# IDC_connectors.net
KiCad netlist of a schematic drawn in Altium Designer
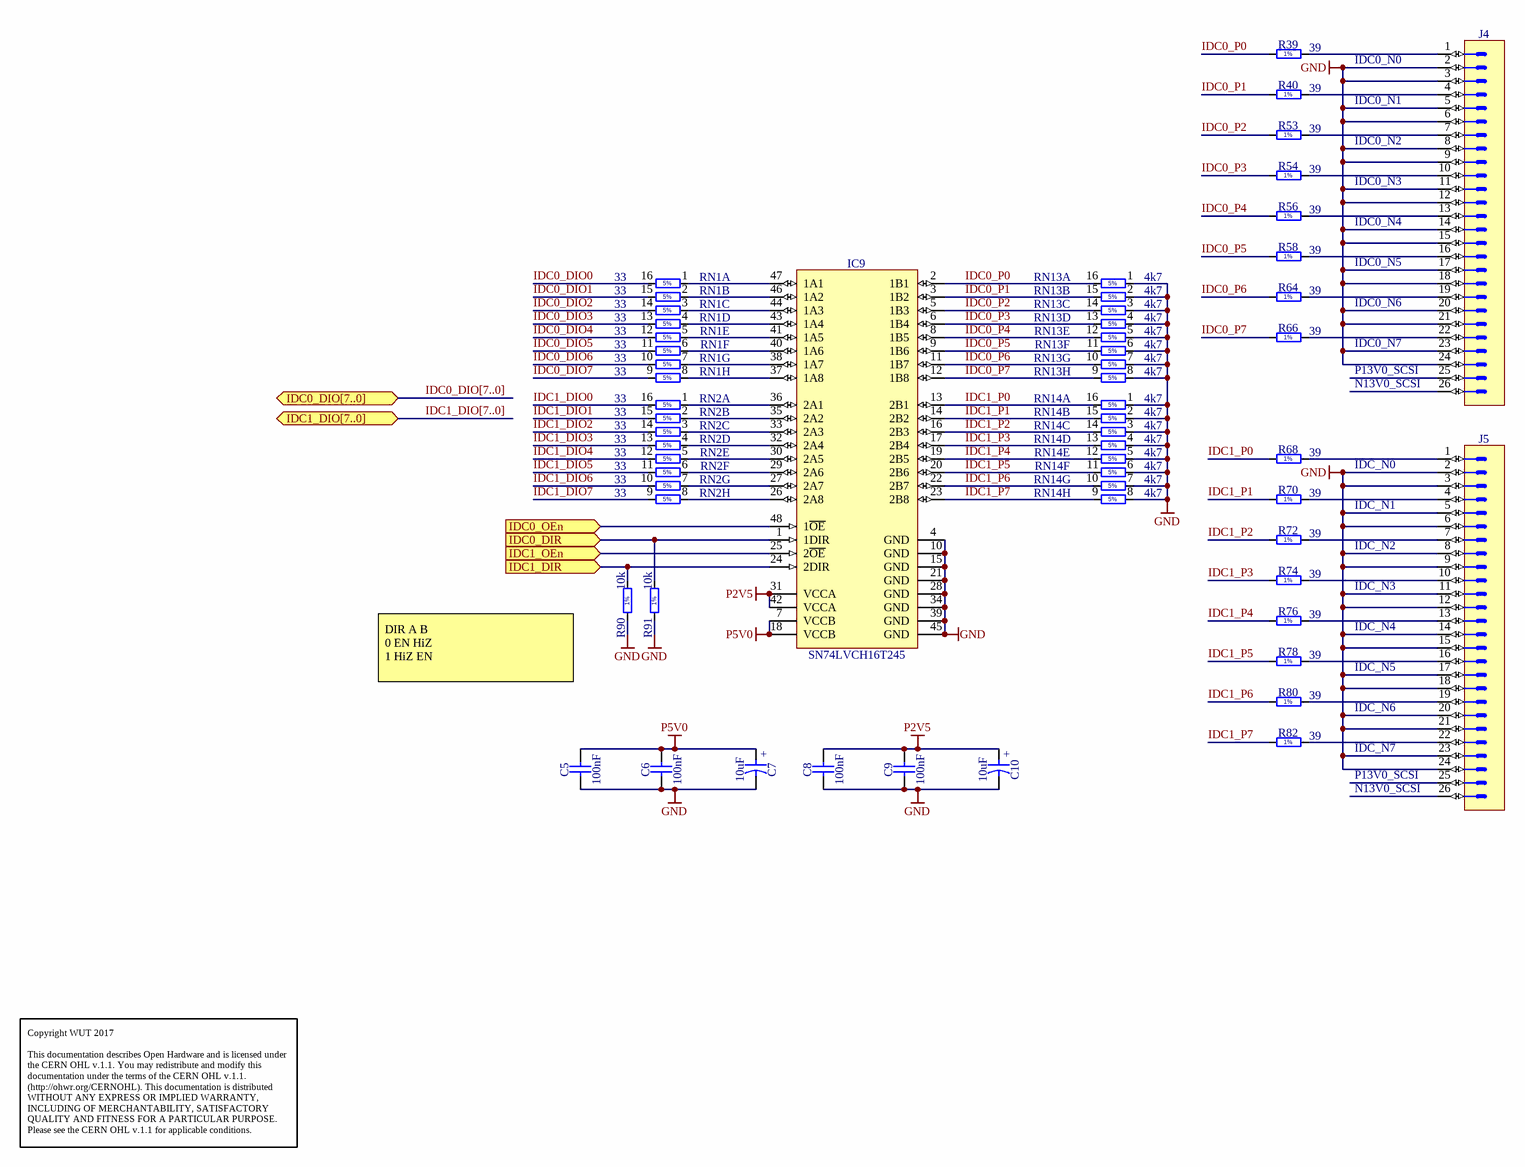
[diagram p0: IDC_connectors.SchDoc]

(export (version "E")
  (design (tool "Eeschema 10.0.6"))
  (components
    (comp (ref "C5")
      (value "100nF")
      (footprint "CAPC1005X55N")
      (description "Non-polarised capacitor")
      (fields
        (field (name "PART NUMBER") "CC0402_100NF_16V_10%_X5R")
        (field (name "VOLTAGE") "16V")
        (field (name "AUTHOR") "CERN DEM JLC")
      )
      (libsource (lib "Capacitors") (part "Capacitor - non polarized"))
    )
    (comp (ref "C6")
      (value "100nF")
      (footprint "CAPC1005X55N")
      (description "Non-polarised capacitor")
      (fields
        (field (name "PART NUMBER") "CC0402_100NF_16V_10%_X5R")
        (field (name "VOLTAGE") "16V")
        (field (name "AUTHOR") "CERN DEM JLC")
      )
      (libsource (lib "Capacitors") (part "Capacitor - non polarized"))
    )
    (comp (ref "C7")
      (value "10uF")
      (footprint "CAPAE430X540N")
      (description "Polarised capacitor")
      (fields
        (field (name "PART NUMBER") "CAE430-540_10UF_16V_20%")
        (field (name "VOLTAGE") "16V")
        (field (name "AUTHOR") "CERN DEM JLC")
      )
      (libsource (lib "Capacitors") (part "Capacitor - polarized"))
    )
    (comp (ref "C8")
      (value "100nF")
      (footprint "CAPC1005X55N")
      (description "Non-polarised capacitor")
      (fields
        (field (name "PART NUMBER") "CC0402_100NF_16V_10%_X5R")
        (field (name "VOLTAGE") "16V")
        (field (name "AUTHOR") "CERN DEM JLC")
      )
      (libsource (lib "Capacitors") (part "Capacitor - non polarized"))
    )
    (comp (ref "C9")
      (value "100nF")
      (footprint "CAPC1005X55N")
      (description "Non-polarised capacitor")
      (fields
        (field (name "PART NUMBER") "CC0402_100NF_16V_10%_X5R")
        (field (name "VOLTAGE") "16V")
        (field (name "AUTHOR") "CERN DEM JLC")
      )
      (libsource (lib "Capacitors") (part "Capacitor - non polarized"))
    )
    (comp (ref "C10")
      (value "10uF")
      (footprint "CAPAE430X540N")
      (description "Polarised capacitor")
      (fields
        (field (name "PART NUMBER") "CAE430-540_10UF_16V_20%")
        (field (name "VOLTAGE") "16V")
        (field (name "AUTHOR") "CERN DEM JLC")
      )
      (libsource (lib "Capacitors") (part "Capacitor - polarized"))
    )
    (comp (ref "IC9")
      (value "SN74LVCH16T245")
      (footprint "SOP50P810X120-48N")
      (description "16-Bit Dual-Supply Bus Transceiver With Configurable Voltage Translation And 3-State Outputs")
      (fields
        (field (name "PART NUMBER") "SN74LVCH16T245DGGR")
        (field (name "MANUFACTURER") "TEXAS INSTRUMENTS")
        (field (name "AUTHOR") "GK")
      )
      (libsource (lib "LIBRARY_SCH") (part "74LVCH16T245"))
    )
    (comp (ref "J4")
      (value "Header 26")
      (footprint "3M_N2526-6003RB")
      (description "Connector 26 Male")
      (fields
        (field (name "PART NUMBER") "3M_N2526-6003RB")
        (field (name "MANUFACTURER") "3M")
        (field (name "AUTHOR") "CERN DEM JLC")
      )
      (libsource (lib "Connectors") (part "Connector 26 Male"))
    )
    (comp (ref "J5")
      (value "Header 26")
      (footprint "3M_N2526-6003RB")
      (description "Connector 26 Male")
      (fields
        (field (name "PART NUMBER") "3M_N2526-6003RB")
        (field (name "MANUFACTURER") "3M")
        (field (name "AUTHOR") "CERN DEM JLC")
      )
      (libsource (lib "Connectors") (part "Connector 26 Male"))
    )
    (comp (ref "R39")
      (value "39")
      (footprint "RESC2012X60N")
      (description "Resistor - 1%")
      (fields
        (field (name "PART NUMBER") "R0805_39R_1%_0.125W_100PPM")
        (field (name "POWER") "0.125W")
        (field (name "AUTHOR") "CERN DEM JLC")
      )
      (libsource (lib "Resistors") (part "Resistor - 1%"))
    )
    (comp (ref "R40")
      (value "39")
      (footprint "RESC2012X60N")
      (description "Resistor - 1%")
      (fields
        (field (name "PART NUMBER") "R0805_39R_1%_0.125W_100PPM")
        (field (name "POWER") "0.125W")
        (field (name "AUTHOR") "CERN DEM JLC")
      )
      (libsource (lib "Resistors") (part "Resistor - 1%"))
    )
    (comp (ref "R53")
      (value "39")
      (footprint "RESC2012X60N")
      (description "Resistor - 1%")
      (fields
        (field (name "PART NUMBER") "R0805_39R_1%_0.125W_100PPM")
        (field (name "POWER") "0.125W")
        (field (name "AUTHOR") "CERN DEM JLC")
      )
      (libsource (lib "Resistors") (part "Resistor - 1%"))
    )
    (comp (ref "R54")
      (value "39")
      (footprint "RESC2012X60N")
      (description "Resistor - 1%")
      (fields
        (field (name "PART NUMBER") "R0805_39R_1%_0.125W_100PPM")
        (field (name "POWER") "0.125W")
        (field (name "AUTHOR") "CERN DEM JLC")
      )
      (libsource (lib "Resistors") (part "Resistor - 1%"))
    )
    (comp (ref "R56")
      (value "39")
      (footprint "RESC2012X60N")
      (description "Resistor - 1%")
      (fields
        (field (name "PART NUMBER") "R0805_39R_1%_0.125W_100PPM")
        (field (name "POWER") "0.125W")
        (field (name "AUTHOR") "CERN DEM JLC")
      )
      (libsource (lib "Resistors") (part "Resistor - 1%"))
    )
    (comp (ref "R58")
      (value "39")
      (footprint "RESC2012X60N")
      (description "Resistor - 1%")
      (fields
        (field (name "PART NUMBER") "R0805_39R_1%_0.125W_100PPM")
        (field (name "POWER") "0.125W")
        (field (name "AUTHOR") "CERN DEM JLC")
      )
      (libsource (lib "Resistors") (part "Resistor - 1%"))
    )
    (comp (ref "R64")
      (value "39")
      (footprint "RESC2012X60N")
      (description "Resistor - 1%")
      (fields
        (field (name "PART NUMBER") "R0805_39R_1%_0.125W_100PPM")
        (field (name "POWER") "0.125W")
        (field (name "AUTHOR") "CERN DEM JLC")
      )
      (libsource (lib "Resistors") (part "Resistor - 1%"))
    )
    (comp (ref "R66")
      (value "39")
      (footprint "RESC2012X60N")
      (description "Resistor - 1%")
      (fields
        (field (name "PART NUMBER") "R0805_39R_1%_0.125W_100PPM")
        (field (name "POWER") "0.125W")
        (field (name "AUTHOR") "CERN DEM JLC")
      )
      (libsource (lib "Resistors") (part "Resistor - 1%"))
    )
    (comp (ref "R68")
      (value "39")
      (footprint "RESC2012X60N")
      (description "Resistor - 1%")
      (fields
        (field (name "PART NUMBER") "R0805_39R_1%_0.125W_100PPM")
        (field (name "POWER") "0.125W")
        (field (name "AUTHOR") "CERN DEM JLC")
      )
      (libsource (lib "Resistors") (part "Resistor - 1%"))
    )
    (comp (ref "R70")
      (value "39")
      (footprint "RESC2012X60N")
      (description "Resistor - 1%")
      (fields
        (field (name "PART NUMBER") "R0805_39R_1%_0.125W_100PPM")
        (field (name "POWER") "0.125W")
        (field (name "AUTHOR") "CERN DEM JLC")
      )
      (libsource (lib "Resistors") (part "Resistor - 1%"))
    )
    (comp (ref "R72")
      (value "39")
      (footprint "RESC2012X60N")
      (description "Resistor - 1%")
      (fields
        (field (name "PART NUMBER") "R0805_39R_1%_0.125W_100PPM")
        (field (name "POWER") "0.125W")
        (field (name "AUTHOR") "CERN DEM JLC")
      )
      (libsource (lib "Resistors") (part "Resistor - 1%"))
    )
    (comp (ref "R74")
      (value "39")
      (footprint "RESC2012X60N")
      (description "Resistor - 1%")
      (fields
        (field (name "PART NUMBER") "R0805_39R_1%_0.125W_100PPM")
        (field (name "POWER") "0.125W")
        (field (name "AUTHOR") "CERN DEM JLC")
      )
      (libsource (lib "Resistors") (part "Resistor - 1%"))
    )
    (comp (ref "R76")
      (value "39")
      (footprint "RESC2012X60N")
      (description "Resistor - 1%")
      (fields
        (field (name "PART NUMBER") "R0805_39R_1%_0.125W_100PPM")
        (field (name "POWER") "0.125W")
        (field (name "AUTHOR") "CERN DEM JLC")
      )
      (libsource (lib "Resistors") (part "Resistor - 1%"))
    )
    (comp (ref "R78")
      (value "39")
      (footprint "RESC2012X60N")
      (description "Resistor - 1%")
      (fields
        (field (name "PART NUMBER") "R0805_39R_1%_0.125W_100PPM")
        (field (name "POWER") "0.125W")
        (field (name "AUTHOR") "CERN DEM JLC")
      )
      (libsource (lib "Resistors") (part "Resistor - 1%"))
    )
    (comp (ref "R80")
      (value "39")
      (footprint "RESC2012X60N")
      (description "Resistor - 1%")
      (fields
        (field (name "PART NUMBER") "R0805_39R_1%_0.125W_100PPM")
        (field (name "POWER") "0.125W")
        (field (name "AUTHOR") "CERN DEM JLC")
      )
      (libsource (lib "Resistors") (part "Resistor - 1%"))
    )
    (comp (ref "R82")
      (value "39")
      (footprint "RESC2012X60N")
      (description "Resistor - 1%")
      (fields
        (field (name "PART NUMBER") "R0805_39R_1%_0.125W_100PPM")
        (field (name "POWER") "0.125W")
        (field (name "AUTHOR") "CERN DEM JLC")
      )
      (libsource (lib "Resistors") (part "Resistor - 1%"))
    )
    (comp (ref "R90")
      (value "10k")
      (footprint "RESC1005X40N")
      (description "Resistor - 1%")
      (fields
        (field (name "PART NUMBER") "R0402_10K_1%_0.0625W_100PPM")
        (field (name "POWER") "0.0625W")
        (field (name "AUTHOR") "CERN DEM JLC")
      )
      (libsource (lib "Resistors") (part "Resistor - 1%"))
    )
    (comp (ref "R91")
      (value "10k")
      (footprint "RESC1005X40N")
      (description "Resistor - 1%")
      (fields
        (field (name "PART NUMBER") "R0402_10K_1%_0.0625W_100PPM")
        (field (name "POWER") "0.0625W")
        (field (name "AUTHOR") "CERN DEM JLC")
      )
      (libsource (lib "Resistors") (part "Resistor - 1%"))
    )
    (comp (ref "RN1")
      (value "33")
      (footprint "RN_YAGEO_YC248")
      (description "DIL16 Resistor Network 8 Isolated Resistor 5%")
      (fields
        (field (name "PART NUMBER") "RN_33R_YAGEO_YC248-JR-0733RL")
        (field (name "POWER") "0.062W")
        (field (name "AUTHOR") "CERN DEM JLC")
      )
      (libsource (lib "Resistors") (part "RN DIL16_8xR_Isolated_5%"))
    )
    (comp (ref "RN2")
      (value "33")
      (footprint "RN_YAGEO_YC248")
      (description "DIL16 Resistor Network 8 Isolated Resistor 5%")
      (fields
        (field (name "PART NUMBER") "RN_33R_YAGEO_YC248-JR-0733RL")
        (field (name "POWER") "0.062W")
        (field (name "AUTHOR") "CERN DEM JLC")
      )
      (libsource (lib "Resistors") (part "RN DIL16_8xR_Isolated_5%"))
    )
    (comp (ref "RN13")
      (value "4k7")
      (footprint "RN_YAGEO_YC248")
      (description "8x Resistor Network  Isolated Resistor 5%")
      (fields
        (field (name "PART NUMBER") "RN_33R_YAGEO_YC248-JR-074K7L")
        (field (name "POWER") "0.062W")
        (field (name "AUTHOR") "GK")
      )
      (libsource (lib "LIBRARY_SCH") (part "RES_RN_4K7_YAGEO_YC248-JR-074K7L"))
    )
    (comp (ref "RN14")
      (value "4k7")
      (footprint "RN_YAGEO_YC248")
      (description "8x Resistor Network  Isolated Resistor 5%")
      (fields
        (field (name "PART NUMBER") "RN_33R_YAGEO_YC248-JR-074K7L")
        (field (name "POWER") "0.062W")
        (field (name "AUTHOR") "GK")
      )
      (libsource (lib "LIBRARY_SCH") (part "RES_RN_4K7_YAGEO_YC248-JR-074K7L"))
    )
  )
  (nets
    (net (code "1") (name "/IDC0_DIO0") (class "Default")
      (node (ref "RN1") (pin "16") (pinfunction "16_16") (pintype "passive"))
    )
    (net (code "2") (name "/IDC0_DIO1") (class "Default")
      (node (ref "RN1") (pin "15") (pinfunction "15_15") (pintype "passive"))
    )
    (net (code "3") (name "/IDC0_DIO2") (class "Default")
      (node (ref "RN1") (pin "14") (pinfunction "14_14") (pintype "passive"))
    )
    (net (code "4") (name "/IDC0_DIO3") (class "Default")
      (node (ref "RN1") (pin "13") (pinfunction "13_13") (pintype "passive"))
    )
    (net (code "5") (name "/IDC0_DIO4") (class "Default")
      (node (ref "RN1") (pin "12") (pinfunction "12_12") (pintype "passive"))
    )
    (net (code "6") (name "/IDC0_DIO5") (class "Default")
      (node (ref "RN1") (pin "11") (pinfunction "11_11") (pintype "passive"))
    )
    (net (code "7") (name "/IDC0_DIO6") (class "Default")
      (node (ref "RN1") (pin "10") (pinfunction "10_10") (pintype "passive"))
    )
    (net (code "8") (name "/IDC0_DIO7") (class "Default")
      (node (ref "RN1") (pin "9") (pinfunction "9_9") (pintype "passive"))
    )
    (net (code "10") (name "/IDC0_DIR") (class "Default")
      (node (ref "IC9") (pin "1") (pinfunction "1DIR_1") (pintype "input"))
      (node (ref "R91") (pin "2") (pinfunction "2_2") (pintype "passive"))
    )
    (net (code "11") (name "/IDC0_OEn") (class "Default")
      (node (ref "IC9") (pin "48") (pinfunction "1~{OE}_48") (pintype "input"))
    )
    (net (code "12") (name "/IDC0_P0") (class "Default")
      (node (ref "IC9") (pin "2") (pinfunction "1B1_2") (pintype "bidirectional"))
      (node (ref "R39") (pin "1") (pinfunction "1_1") (pintype "passive"))
      (node (ref "RN13") (pin "16") (pinfunction "16_16") (pintype "passive"))
    )
    (net (code "13") (name "/IDC0_P1") (class "Default")
      (node (ref "IC9") (pin "3") (pinfunction "1B2_3") (pintype "bidirectional"))
      (node (ref "R40") (pin "1") (pinfunction "1_1") (pintype "passive"))
      (node (ref "RN13") (pin "15") (pinfunction "15_15") (pintype "passive"))
    )
    (net (code "14") (name "/IDC0_P2") (class "Default")
      (node (ref "IC9") (pin "5") (pinfunction "1B3_5") (pintype "bidirectional"))
      (node (ref "R53") (pin "1") (pinfunction "1_1") (pintype "passive"))
      (node (ref "RN13") (pin "14") (pinfunction "14_14") (pintype "passive"))
    )
    (net (code "15") (name "/IDC0_P3") (class "Default")
      (node (ref "IC9") (pin "6") (pinfunction "1B4_6") (pintype "bidirectional"))
      (node (ref "R54") (pin "1") (pinfunction "1_1") (pintype "passive"))
      (node (ref "RN13") (pin "13") (pinfunction "13_13") (pintype "passive"))
    )
    (net (code "16") (name "/IDC0_P4") (class "Default")
      (node (ref "IC9") (pin "8") (pinfunction "1B5_8") (pintype "bidirectional"))
      (node (ref "R56") (pin "1") (pinfunction "1_1") (pintype "passive"))
      (node (ref "RN13") (pin "12") (pinfunction "12_12") (pintype "passive"))
    )
    (net (code "17") (name "/IDC0_P5") (class "Default")
      (node (ref "IC9") (pin "9") (pinfunction "1B6_9") (pintype "bidirectional"))
      (node (ref "R58") (pin "1") (pinfunction "1_1") (pintype "passive"))
      (node (ref "RN13") (pin "11") (pinfunction "11_11") (pintype "passive"))
    )
    (net (code "18") (name "/IDC0_P6") (class "Default")
      (node (ref "IC9") (pin "11") (pinfunction "1B7_11") (pintype "bidirectional"))
      (node (ref "R64") (pin "1") (pinfunction "1_1") (pintype "passive"))
      (node (ref "RN13") (pin "10") (pinfunction "10_10") (pintype "passive"))
    )
    (net (code "19") (name "/IDC0_P7") (class "Default")
      (node (ref "IC9") (pin "12") (pinfunction "1B8_12") (pintype "bidirectional"))
      (node (ref "R66") (pin "1") (pinfunction "1_1") (pintype "passive"))
      (node (ref "RN13") (pin "9") (pinfunction "9_9") (pintype "passive"))
    )
    (net (code "20") (name "/IDC1_DIO0") (class "Default")
      (node (ref "RN2") (pin "16") (pinfunction "16_16") (pintype "passive"))
    )
    (net (code "21") (name "/IDC1_DIO1") (class "Default")
      (node (ref "RN2") (pin "15") (pinfunction "15_15") (pintype "passive"))
    )
    (net (code "22") (name "/IDC1_DIO2") (class "Default")
      (node (ref "RN2") (pin "14") (pinfunction "14_14") (pintype "passive"))
    )
    (net (code "23") (name "/IDC1_DIO3") (class "Default")
      (node (ref "RN2") (pin "13") (pinfunction "13_13") (pintype "passive"))
    )
    (net (code "24") (name "/IDC1_DIO4") (class "Default")
      (node (ref "RN2") (pin "12") (pinfunction "12_12") (pintype "passive"))
    )
    (net (code "25") (name "/IDC1_DIO5") (class "Default")
      (node (ref "RN2") (pin "11") (pinfunction "11_11") (pintype "passive"))
    )
    (net (code "26") (name "/IDC1_DIO6") (class "Default")
      (node (ref "RN2") (pin "10") (pinfunction "10_10") (pintype "passive"))
    )
    (net (code "27") (name "/IDC1_DIO7") (class "Default")
      (node (ref "RN2") (pin "9") (pinfunction "9_9") (pintype "passive"))
    )
    (net (code "29") (name "/IDC1_DIR") (class "Default")
      (node (ref "IC9") (pin "24") (pinfunction "2DIR_24") (pintype "input"))
      (node (ref "R90") (pin "2") (pinfunction "2_2") (pintype "passive"))
    )
    (net (code "30") (name "/IDC1_OEn") (class "Default")
      (node (ref "IC9") (pin "25") (pinfunction "2~{OE}_25") (pintype "input"))
    )
    (net (code "31") (name "/IDC1_P0") (class "Default")
      (node (ref "IC9") (pin "13") (pinfunction "2B1_13") (pintype "bidirectional"))
      (node (ref "R68") (pin "1") (pinfunction "1_1") (pintype "passive"))
      (node (ref "RN14") (pin "16") (pinfunction "16_16") (pintype "passive"))
    )
    (net (code "32") (name "/IDC1_P1") (class "Default")
      (node (ref "IC9") (pin "14") (pinfunction "2B2_14") (pintype "bidirectional"))
      (node (ref "R70") (pin "1") (pinfunction "1_1") (pintype "passive"))
      (node (ref "RN14") (pin "15") (pinfunction "15_15") (pintype "passive"))
    )
    (net (code "33") (name "/IDC1_P2") (class "Default")
      (node (ref "IC9") (pin "16") (pinfunction "2B3_16") (pintype "bidirectional"))
      (node (ref "R72") (pin "1") (pinfunction "1_1") (pintype "passive"))
      (node (ref "RN14") (pin "14") (pinfunction "14_14") (pintype "passive"))
    )
    (net (code "34") (name "/IDC1_P3") (class "Default")
      (node (ref "IC9") (pin "17") (pinfunction "2B4_17") (pintype "bidirectional"))
      (node (ref "R74") (pin "1") (pinfunction "1_1") (pintype "passive"))
      (node (ref "RN14") (pin "13") (pinfunction "13_13") (pintype "passive"))
    )
    (net (code "35") (name "/IDC1_P4") (class "Default")
      (node (ref "IC9") (pin "19") (pinfunction "2B5_19") (pintype "bidirectional"))
      (node (ref "R76") (pin "1") (pinfunction "1_1") (pintype "passive"))
      (node (ref "RN14") (pin "12") (pinfunction "12_12") (pintype "passive"))
    )
    (net (code "36") (name "/IDC1_P5") (class "Default")
      (node (ref "IC9") (pin "20") (pinfunction "2B6_20") (pintype "bidirectional"))
      (node (ref "R78") (pin "1") (pinfunction "1_1") (pintype "passive"))
      (node (ref "RN14") (pin "11") (pinfunction "11_11") (pintype "passive"))
    )
    (net (code "37") (name "/IDC1_P6") (class "Default")
      (node (ref "IC9") (pin "22") (pinfunction "2B7_22") (pintype "bidirectional"))
      (node (ref "R80") (pin "1") (pinfunction "1_1") (pintype "passive"))
      (node (ref "RN14") (pin "10") (pinfunction "10_10") (pintype "passive"))
    )
    (net (code "38") (name "/IDC1_P7") (class "Default")
      (node (ref "IC9") (pin "23") (pinfunction "2B8_23") (pintype "bidirectional"))
      (node (ref "R82") (pin "1") (pinfunction "1_1") (pintype "passive"))
      (node (ref "RN14") (pin "9") (pinfunction "9_9") (pintype "passive"))
    )
    (net (code "39") (name "GND") (class "Default")
      (node (ref "C10") (pin "2") (pinfunction "2_2") (pintype "passive"))
      (node (ref "C5") (pin "1") (pinfunction "1_1") (pintype "passive"))
      (node (ref "C6") (pin "1") (pinfunction "1_1") (pintype "passive"))
      (node (ref "C7") (pin "2") (pinfunction "2_2") (pintype "passive"))
      (node (ref "C8") (pin "1") (pinfunction "1_1") (pintype "passive"))
      (node (ref "C9") (pin "1") (pinfunction "1_1") (pintype "passive"))
      (node (ref "IC9") (pin "10") (pinfunction "GND_10") (pintype "power_in"))
      (node (ref "IC9") (pin "15") (pinfunction "GND_15") (pintype "power_in"))
      (node (ref "IC9") (pin "21") (pinfunction "GND_21") (pintype "power_in"))
      (node (ref "IC9") (pin "28") (pinfunction "GND_28") (pintype "power_in"))
      (node (ref "IC9") (pin "34") (pinfunction "GND_34") (pintype "power_in"))
      (node (ref "IC9") (pin "39") (pinfunction "GND_39") (pintype "power_in"))
      (node (ref "IC9") (pin "4") (pinfunction "GND_4") (pintype "power_in"))
      (node (ref "IC9") (pin "45") (pinfunction "GND_45") (pintype "power_in"))
      (node (ref "J4") (pin "11") (pinfunction "11_11") (pintype "bidirectional"))
      (node (ref "J4") (pin "12") (pinfunction "12_12") (pintype "bidirectional"))
      (node (ref "J4") (pin "14") (pinfunction "14_14") (pintype "bidirectional"))
      (node (ref "J4") (pin "15") (pinfunction "15_15") (pintype "bidirectional"))
      (node (ref "J4") (pin "17") (pinfunction "17_17") (pintype "bidirectional"))
      (node (ref "J4") (pin "18") (pinfunction "18_18") (pintype "bidirectional"))
      (node (ref "J4") (pin "2") (pinfunction "2_2") (pintype "bidirectional"))
      (node (ref "J4") (pin "20") (pinfunction "20_20") (pintype "bidirectional"))
      (node (ref "J4") (pin "21") (pinfunction "21_21") (pintype "bidirectional"))
      (node (ref "J4") (pin "23") (pinfunction "23_23") (pintype "bidirectional"))
      (node (ref "J4") (pin "24") (pinfunction "24_24") (pintype "bidirectional"))
      (node (ref "J4") (pin "3") (pinfunction "3_3") (pintype "bidirectional"))
      (node (ref "J4") (pin "5") (pinfunction "5_5") (pintype "bidirectional"))
      (node (ref "J4") (pin "6") (pinfunction "6_6") (pintype "bidirectional"))
      (node (ref "J4") (pin "8") (pinfunction "8_8") (pintype "bidirectional"))
      (node (ref "J4") (pin "9") (pinfunction "9_9") (pintype "bidirectional"))
      (node (ref "J5") (pin "11") (pinfunction "11_11") (pintype "bidirectional"))
      (node (ref "J5") (pin "12") (pinfunction "12_12") (pintype "bidirectional"))
      (node (ref "J5") (pin "14") (pinfunction "14_14") (pintype "bidirectional"))
      (node (ref "J5") (pin "15") (pinfunction "15_15") (pintype "bidirectional"))
      (node (ref "J5") (pin "17") (pinfunction "17_17") (pintype "bidirectional"))
      (node (ref "J5") (pin "18") (pinfunction "18_18") (pintype "bidirectional"))
      (node (ref "J5") (pin "2") (pinfunction "2_2") (pintype "bidirectional"))
      (node (ref "J5") (pin "20") (pinfunction "20_20") (pintype "bidirectional"))
      (node (ref "J5") (pin "21") (pinfunction "21_21") (pintype "bidirectional"))
      (node (ref "J5") (pin "23") (pinfunction "23_23") (pintype "bidirectional"))
      (node (ref "J5") (pin "24") (pinfunction "24_24") (pintype "bidirectional"))
      (node (ref "J5") (pin "3") (pinfunction "3_3") (pintype "bidirectional"))
      (node (ref "J5") (pin "5") (pinfunction "5_5") (pintype "bidirectional"))
      (node (ref "J5") (pin "6") (pinfunction "6_6") (pintype "bidirectional"))
      (node (ref "J5") (pin "8") (pinfunction "8_8") (pintype "bidirectional"))
      (node (ref "J5") (pin "9") (pinfunction "9_9") (pintype "bidirectional"))
      (node (ref "R90") (pin "1") (pinfunction "1_1") (pintype "passive"))
      (node (ref "R91") (pin "1") (pinfunction "1_1") (pintype "passive"))
      (node (ref "RN13") (pin "1") (pinfunction "1_1") (pintype "passive"))
      (node (ref "RN13") (pin "2") (pinfunction "2_2") (pintype "passive"))
      (node (ref "RN13") (pin "3") (pinfunction "3_3") (pintype "passive"))
      (node (ref "RN13") (pin "4") (pinfunction "4_4") (pintype "passive"))
      (node (ref "RN13") (pin "5") (pinfunction "5_5") (pintype "passive"))
      (node (ref "RN13") (pin "6") (pinfunction "6_6") (pintype "passive"))
      (node (ref "RN13") (pin "7") (pinfunction "7_7") (pintype "passive"))
      (node (ref "RN13") (pin "8") (pinfunction "8_8") (pintype "passive"))
      (node (ref "RN14") (pin "1") (pinfunction "1_1") (pintype "passive"))
      (node (ref "RN14") (pin "2") (pinfunction "2_2") (pintype "passive"))
      (node (ref "RN14") (pin "3") (pinfunction "3_3") (pintype "passive"))
      (node (ref "RN14") (pin "4") (pinfunction "4_4") (pintype "passive"))
      (node (ref "RN14") (pin "5") (pinfunction "5_5") (pintype "passive"))
      (node (ref "RN14") (pin "6") (pinfunction "6_6") (pintype "passive"))
      (node (ref "RN14") (pin "7") (pinfunction "7_7") (pintype "passive"))
      (node (ref "RN14") (pin "8") (pinfunction "8_8") (pintype "passive"))
    )
    (net (code "40") (name "Net-(IC9-1A1)") (class "Default")
      (node (ref "IC9") (pin "47") (pinfunction "1A1_47") (pintype "bidirectional"))
      (node (ref "RN1") (pin "1") (pinfunction "1_1") (pintype "passive"))
    )
    (net (code "41") (name "Net-(IC9-1A2)") (class "Default")
      (node (ref "IC9") (pin "46") (pinfunction "1A2_46") (pintype "bidirectional"))
      (node (ref "RN1") (pin "2") (pinfunction "2_2") (pintype "passive"))
    )
    (net (code "42") (name "Net-(IC9-1A3)") (class "Default")
      (node (ref "IC9") (pin "44") (pinfunction "1A3_44") (pintype "bidirectional"))
      (node (ref "RN1") (pin "3") (pinfunction "3_3") (pintype "passive"))
    )
    (net (code "43") (name "Net-(IC9-1A4)") (class "Default")
      (node (ref "IC9") (pin "43") (pinfunction "1A4_43") (pintype "bidirectional"))
      (node (ref "RN1") (pin "4") (pinfunction "4_4") (pintype "passive"))
    )
    (net (code "44") (name "Net-(IC9-1A5)") (class "Default")
      (node (ref "IC9") (pin "41") (pinfunction "1A5_41") (pintype "bidirectional"))
      (node (ref "RN1") (pin "5") (pinfunction "5_5") (pintype "passive"))
    )
    (net (code "45") (name "Net-(IC9-1A6)") (class "Default")
      (node (ref "IC9") (pin "40") (pinfunction "1A6_40") (pintype "bidirectional"))
      (node (ref "RN1") (pin "6") (pinfunction "6_6") (pintype "passive"))
    )
    (net (code "46") (name "Net-(IC9-1A7)") (class "Default")
      (node (ref "IC9") (pin "38") (pinfunction "1A7_38") (pintype "bidirectional"))
      (node (ref "RN1") (pin "7") (pinfunction "7_7") (pintype "passive"))
    )
    (net (code "47") (name "Net-(IC9-1A8)") (class "Default")
      (node (ref "IC9") (pin "37") (pinfunction "1A8_37") (pintype "bidirectional"))
      (node (ref "RN1") (pin "8") (pinfunction "8_8") (pintype "passive"))
    )
    (net (code "48") (name "Net-(IC9-2A1)") (class "Default")
      (node (ref "IC9") (pin "36") (pinfunction "2A1_36") (pintype "bidirectional"))
      (node (ref "RN2") (pin "1") (pinfunction "1_1") (pintype "passive"))
    )
    (net (code "49") (name "Net-(IC9-2A2)") (class "Default")
      (node (ref "IC9") (pin "35") (pinfunction "2A2_35") (pintype "bidirectional"))
      (node (ref "RN2") (pin "2") (pinfunction "2_2") (pintype "passive"))
    )
    (net (code "50") (name "Net-(IC9-2A3)") (class "Default")
      (node (ref "IC9") (pin "33") (pinfunction "2A3_33") (pintype "bidirectional"))
      (node (ref "RN2") (pin "3") (pinfunction "3_3") (pintype "passive"))
    )
    (net (code "51") (name "Net-(IC9-2A4)") (class "Default")
      (node (ref "IC9") (pin "32") (pinfunction "2A4_32") (pintype "bidirectional"))
      (node (ref "RN2") (pin "4") (pinfunction "4_4") (pintype "passive"))
    )
    (net (code "52") (name "Net-(IC9-2A5)") (class "Default")
      (node (ref "IC9") (pin "30") (pinfunction "2A5_30") (pintype "bidirectional"))
      (node (ref "RN2") (pin "5") (pinfunction "5_5") (pintype "passive"))
    )
    (net (code "53") (name "Net-(IC9-2A6)") (class "Default")
      (node (ref "IC9") (pin "29") (pinfunction "2A6_29") (pintype "bidirectional"))
      (node (ref "RN2") (pin "6") (pinfunction "6_6") (pintype "passive"))
    )
    (net (code "54") (name "Net-(IC9-2A7)") (class "Default")
      (node (ref "IC9") (pin "27") (pinfunction "2A7_27") (pintype "bidirectional"))
      (node (ref "RN2") (pin "7") (pinfunction "7_7") (pintype "passive"))
    )
    (net (code "55") (name "Net-(IC9-2A8)") (class "Default")
      (node (ref "IC9") (pin "26") (pinfunction "2A8_26") (pintype "bidirectional"))
      (node (ref "RN2") (pin "8") (pinfunction "8_8") (pintype "passive"))
    )
    (net (code "56") (name "Net-(J4-Pad1)") (class "Default")
      (node (ref "J4") (pin "1") (pinfunction "1_1") (pintype "bidirectional"))
      (node (ref "R39") (pin "2") (pinfunction "2_2") (pintype "passive"))
    )
    (net (code "57") (name "Net-(J4-Pad4)") (class "Default")
      (node (ref "J4") (pin "4") (pinfunction "4_4") (pintype "bidirectional"))
      (node (ref "R40") (pin "2") (pinfunction "2_2") (pintype "passive"))
    )
    (net (code "58") (name "Net-(J4-Pad7)") (class "Default")
      (node (ref "J4") (pin "7") (pinfunction "7_7") (pintype "bidirectional"))
      (node (ref "R53") (pin "2") (pinfunction "2_2") (pintype "passive"))
    )
    (net (code "59") (name "Net-(J4-Pad10)") (class "Default")
      (node (ref "J4") (pin "10") (pinfunction "10_10") (pintype "bidirectional"))
      (node (ref "R54") (pin "2") (pinfunction "2_2") (pintype "passive"))
    )
    (net (code "60") (name "Net-(J4-Pad13)") (class "Default")
      (node (ref "J4") (pin "13") (pinfunction "13_13") (pintype "bidirectional"))
      (node (ref "R56") (pin "2") (pinfunction "2_2") (pintype "passive"))
    )
    (net (code "61") (name "Net-(J4-Pad16)") (class "Default")
      (node (ref "J4") (pin "16") (pinfunction "16_16") (pintype "bidirectional"))
      (node (ref "R58") (pin "2") (pinfunction "2_2") (pintype "passive"))
    )
    (net (code "62") (name "Net-(J4-Pad19)") (class "Default")
      (node (ref "J4") (pin "19") (pinfunction "19_19") (pintype "bidirectional"))
      (node (ref "R64") (pin "2") (pinfunction "2_2") (pintype "passive"))
    )
    (net (code "63") (name "Net-(J4-Pad22)") (class "Default")
      (node (ref "J4") (pin "22") (pinfunction "22_22") (pintype "bidirectional"))
      (node (ref "R66") (pin "2") (pinfunction "2_2") (pintype "passive"))
    )
    (net (code "64") (name "Net-(J5-Pad1)") (class "Default")
      (node (ref "J5") (pin "1") (pinfunction "1_1") (pintype "bidirectional"))
      (node (ref "R68") (pin "2") (pinfunction "2_2") (pintype "passive"))
    )
    (net (code "65") (name "Net-(J5-Pad4)") (class "Default")
      (node (ref "J5") (pin "4") (pinfunction "4_4") (pintype "bidirectional"))
      (node (ref "R70") (pin "2") (pinfunction "2_2") (pintype "passive"))
    )
    (net (code "66") (name "Net-(J5-Pad7)") (class "Default")
      (node (ref "J5") (pin "7") (pinfunction "7_7") (pintype "bidirectional"))
      (node (ref "R72") (pin "2") (pinfunction "2_2") (pintype "passive"))
    )
    (net (code "67") (name "Net-(J5-Pad10)") (class "Default")
      (node (ref "J5") (pin "10") (pinfunction "10_10") (pintype "bidirectional"))
      (node (ref "R74") (pin "2") (pinfunction "2_2") (pintype "passive"))
    )
    (net (code "68") (name "Net-(J5-Pad13)") (class "Default")
      (node (ref "J5") (pin "13") (pinfunction "13_13") (pintype "bidirectional"))
      (node (ref "R76") (pin "2") (pinfunction "2_2") (pintype "passive"))
    )
    (net (code "69") (name "Net-(J5-Pad16)") (class "Default")
      (node (ref "J5") (pin "16") (pinfunction "16_16") (pintype "bidirectional"))
      (node (ref "R78") (pin "2") (pinfunction "2_2") (pintype "passive"))
    )
    (net (code "70") (name "Net-(J5-Pad19)") (class "Default")
      (node (ref "J5") (pin "19") (pinfunction "19_19") (pintype "bidirectional"))
      (node (ref "R80") (pin "2") (pinfunction "2_2") (pintype "passive"))
    )
    (net (code "71") (name "Net-(J5-Pad22)") (class "Default")
      (node (ref "J5") (pin "22") (pinfunction "22_22") (pintype "bidirectional"))
      (node (ref "R82") (pin "2") (pinfunction "2_2") (pintype "passive"))
    )
    (net (code "72") (name "P2V5") (class "Default")
      (node (ref "C10") (pin "1") (pinfunction "1_1") (pintype "passive"))
      (node (ref "C8") (pin "2") (pinfunction "2_2") (pintype "passive"))
      (node (ref "C9") (pin "2") (pinfunction "2_2") (pintype "passive"))
      (node (ref "IC9") (pin "31") (pinfunction "VCCA_31") (pintype "power_in"))
      (node (ref "IC9") (pin "42") (pinfunction "VCCA_42") (pintype "power_in"))
    )
    (net (code "73") (name "P5V0") (class "Default")
      (node (ref "C5") (pin "2") (pinfunction "2_2") (pintype "passive"))
      (node (ref "C6") (pin "2") (pinfunction "2_2") (pintype "passive"))
      (node (ref "C7") (pin "1") (pinfunction "1_1") (pintype "passive"))
      (node (ref "IC9") (pin "18") (pinfunction "VCCB_18") (pintype "power_in"))
      (node (ref "IC9") (pin "7") (pinfunction "VCCB_7") (pintype "power_in"))
    )
    (net (code "74") (name "unconnected-(J4-Pad25)") (class "Default")
      (node (ref "J4") (pin "25") (pinfunction "25_25") (pintype "bidirectional"))
    )
    (net (code "75") (name "unconnected-(J4-Pad26)") (class "Default")
      (node (ref "J4") (pin "26") (pinfunction "26_26") (pintype "bidirectional"))
    )
    (net (code "76") (name "unconnected-(J5-Pad25)") (class "Default")
      (node (ref "J5") (pin "25") (pinfunction "25_25") (pintype "bidirectional"))
    )
    (net (code "77") (name "unconnected-(J5-Pad26)") (class "Default")
      (node (ref "J5") (pin "26") (pinfunction "26_26") (pintype "bidirectional"))
    )
  )
)
